# 14_Clocks.net
KiCad netlist of a schematic drawn in Altium Designer
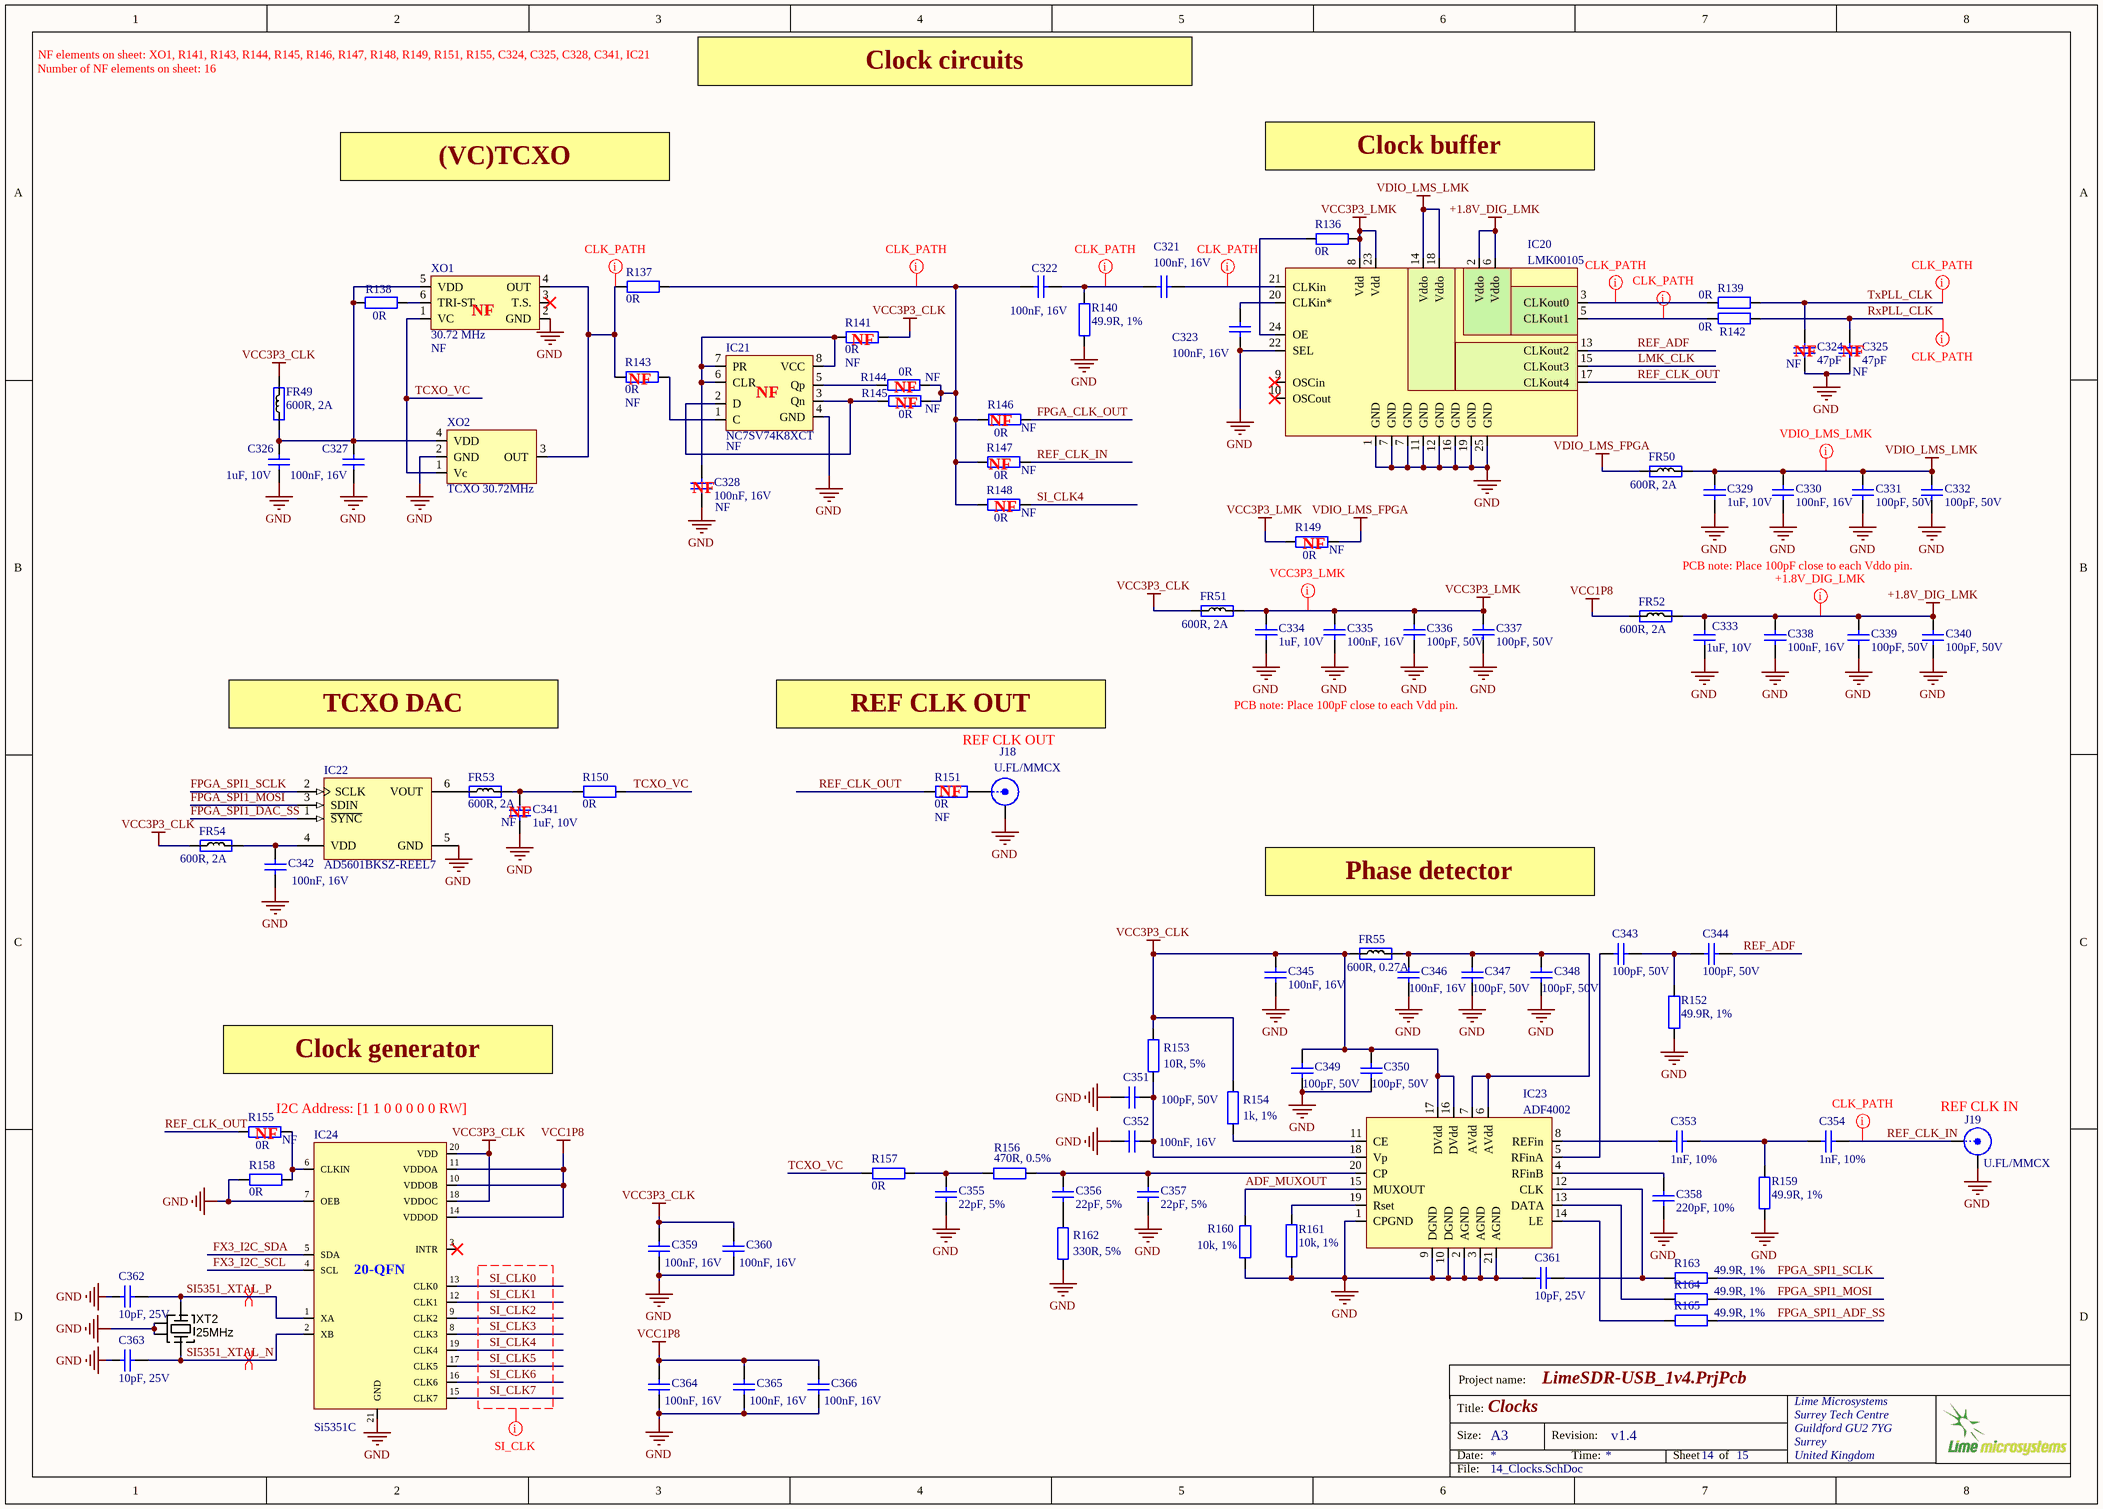
[diagram p0: 14_Clocks.SchDoc]

(export (version "E")
  (design (tool "Eeschema 10.0.6"))
  (components
    (comp (ref "C321")
      (value "100nF, 16V")
      (footprint "CAP0402")
      (fields
        (field (name "MANUFACTURER") "Murata Electronics")
        (field (name "TOLERANCE") "10 %")
        (field (name "MANUFACTURER PART NUMBER") "GRM155R71C104KA88D")
      )
      (libsource (lib "LimeMicroAltiumLib_schLib") (part "Cap_0402"))
    )
    (comp (ref "C322")
      (value "100nF, 16V")
      (footprint "CAP0402")
      (fields
        (field (name "MANUFACTURER") "Murata Electronics")
        (field (name "TOLERANCE") "10 %")
        (field (name "MANUFACTURER PART NUMBER") "GRM155R71C104KA88D")
      )
      (libsource (lib "LimeMicroAltiumLib_schLib") (part "Cap_0402"))
    )
    (comp (ref "C323")
      (value "100nF, 16V")
      (footprint "CAP0402")
      (fields
        (field (name "MANUFACTURER") "Murata Electronics")
        (field (name "TOLERANCE") "10 %")
        (field (name "MANUFACTURER PART NUMBER") "GRM155R71C104KA88D")
      )
      (libsource (lib "LimeMicroAltiumLib_schLib") (part "Cap_0402"))
    )
    (comp (ref "C324")
      (value "47pF")
      (footprint "CAP0402")
      (fields
        (field (name "TOLERANCE") "±1%")
        (field (name "MANUFACTURER") "TDK Corporation")
        (field (name "ASSEMBLY INFO") "NF")
      )
      (libsource (lib "LimeMicroAltiumLib_schLib") (part "Cap_0402"))
    )
    (comp (ref "C325")
      (value "47pF")
      (footprint "CAP0402")
      (fields
        (field (name "TOLERANCE") "±1%")
        (field (name "MANUFACTURER") "TDK Corporation")
        (field (name "ASSEMBLY INFO") "NF")
      )
      (libsource (lib "LimeMicroAltiumLib_schLib") (part "Cap_0402"))
    )
    (comp (ref "C326")
      (value "1uF, 10V")
      (footprint "CAP0402")
      (fields (field (name "MANUFACTURER") "TDK"))
      (libsource (lib "LimeMicroAltiumLib_schLib") (part "Cap_0402"))
    )
    (comp (ref "C327")
      (value "100nF, 16V")
      (footprint "CAP0402")
      (fields
        (field (name "MANUFACTURER") "Murata Electronics")
        (field (name "TOLERANCE") "10 %")
        (field (name "MANUFACTURER PART NUMBER") "GRM155R71C104KA88D")
      )
      (libsource (lib "LimeMicroAltiumLib_schLib") (part "Cap_0402"))
    )
    (comp (ref "C328")
      (value "100nF, 16V")
      (footprint "CAP0402")
      (fields
        (field (name "ASSEMBLY INFO") "NF")
        (field (name "MANUFACTURER") "Murata Electronics")
        (field (name "TOLERANCE") "10 %")
        (field (name "MANUFACTURER PART NUMBER") "GRM155R71C104KA88D")
      )
      (libsource (lib "LimeMicroAltiumLib_schLib") (part "Cap_0402"))
    )
    (comp (ref "C329")
      (value "1uF, 10V")
      (footprint "CAP0402")
      (fields (field (name "MANUFACTURER") "TDK"))
      (libsource (lib "LimeMicroAltiumLib_schLib") (part "Cap_0402"))
    )
    (comp (ref "C330")
      (value "100nF, 16V")
      (footprint "CAP0402")
      (fields
        (field (name "MANUFACTURER") "Murata Electronics")
        (field (name "TOLERANCE") "10 %")
        (field (name "MANUFACTURER PART NUMBER") "GRM155R71C104KA88D")
      )
      (libsource (lib "LimeMicroAltiumLib_schLib") (part "Cap_0402"))
    )
    (comp (ref "C331")
      (value "100pF, 50V")
      (footprint "CAP0402")
      (fields (field (name "MANUFACTURER") "Yageo") (field (name "TOLERANCE") "±5%"))
      (libsource (lib "LimeMicroAltiumLib_schLib") (part "Cap_0402"))
    )
    (comp (ref "C332")
      (value "100pF, 50V")
      (footprint "CAP0402")
      (fields (field (name "MANUFACTURER") "Yageo") (field (name "TOLERANCE") "±5%"))
      (libsource (lib "LimeMicroAltiumLib_schLib") (part "Cap_0402"))
    )
    (comp (ref "C333")
      (value "1uF, 10V")
      (footprint "CAP0402")
      (fields (field (name "MANUFACTURER") "TDK"))
      (libsource (lib "LimeMicroAltiumLib_schLib") (part "Cap_0402"))
    )
    (comp (ref "C334")
      (value "1uF, 10V")
      (footprint "CAP0402")
      (fields (field (name "MANUFACTURER") "TDK"))
      (libsource (lib "LimeMicroAltiumLib_schLib") (part "Cap_0402"))
    )
    (comp (ref "C335")
      (value "100nF, 16V")
      (footprint "CAP0402")
      (fields
        (field (name "MANUFACTURER") "Murata Electronics")
        (field (name "TOLERANCE") "10 %")
        (field (name "MANUFACTURER PART NUMBER") "GRM155R71C104KA88D")
      )
      (libsource (lib "LimeMicroAltiumLib_schLib") (part "Cap_0402"))
    )
    (comp (ref "C336")
      (value "100pF, 50V")
      (footprint "CAP0402")
      (fields (field (name "MANUFACTURER") "Yageo") (field (name "TOLERANCE") "±5%"))
      (libsource (lib "LimeMicroAltiumLib_schLib") (part "Cap_0402"))
    )
    (comp (ref "C337")
      (value "100pF, 50V")
      (footprint "CAP0402")
      (fields (field (name "MANUFACTURER") "Yageo") (field (name "TOLERANCE") "±5%"))
      (libsource (lib "LimeMicroAltiumLib_schLib") (part "Cap_0402"))
    )
    (comp (ref "C338")
      (value "100nF, 16V")
      (footprint "CAP0402")
      (fields
        (field (name "MANUFACTURER") "Murata Electronics")
        (field (name "TOLERANCE") "10 %")
        (field (name "MANUFACTURER PART NUMBER") "GRM155R71C104KA88D")
      )
      (libsource (lib "LimeMicroAltiumLib_schLib") (part "Cap_0402"))
    )
    (comp (ref "C339")
      (value "100pF, 50V")
      (footprint "CAP0402")
      (fields (field (name "MANUFACTURER") "Yageo") (field (name "TOLERANCE") "±5%"))
      (libsource (lib "LimeMicroAltiumLib_schLib") (part "Cap_0402"))
    )
    (comp (ref "C340")
      (value "100pF, 50V")
      (footprint "CAP0402")
      (fields (field (name "MANUFACTURER") "Yageo") (field (name "TOLERANCE") "±5%"))
      (libsource (lib "LimeMicroAltiumLib_schLib") (part "Cap_0402"))
    )
    (comp (ref "C341")
      (value "1uF, 10V")
      (footprint "CAP0402")
      (fields (field (name "ASSEMBLY INFO") "NF") (field (name "MANUFACTURER") "TDK"))
      (libsource (lib "LimeMicroAltiumLib_schLib") (part "Cap_0402"))
    )
    (comp (ref "C342")
      (value "100nF, 16V")
      (footprint "CAP0402")
      (fields
        (field (name "TOLERANCE") "10 %")
        (field (name "MANUFACTURER") "Murata Electronics")
        (field (name "MANUFACTURER PART NUMBER") "GRM155R71C104KA88D")
      )
      (libsource (lib "LimeFPGAboard_schLib") (part "Cap_0603"))
    )
    (comp (ref "C343")
      (value "100pF, 50V")
      (footprint "CAP0402")
      (fields (field (name "MANUFACTURER") "Yageo") (field (name "TOLERANCE") "±5%"))
      (libsource (lib "LimeMicroAltiumLib_schLib") (part "Cap_0402"))
    )
    (comp (ref "C344")
      (value "100pF, 50V")
      (footprint "CAP0402")
      (fields (field (name "MANUFACTURER") "Yageo") (field (name "TOLERANCE") "±5%"))
      (libsource (lib "LimeMicroAltiumLib_schLib") (part "Cap_0402"))
    )
    (comp (ref "C345")
      (value "100nF, 16V")
      (footprint "CAP0402")
      (fields
        (field (name "MANUFACTURER") "Murata Electronics")
        (field (name "TOLERANCE") "10 %")
        (field (name "MANUFACTURER PART NUMBER") "GRM155R71C104KA88D")
      )
      (libsource (lib "LimeMicroAltiumLib_schLib") (part "Cap_0402"))
    )
    (comp (ref "C346")
      (value "100nF, 16V")
      (footprint "CAP0402")
      (fields
        (field (name "MANUFACTURER") "Murata Electronics")
        (field (name "TOLERANCE") "10 %")
        (field (name "MANUFACTURER PART NUMBER") "GRM155R71C104KA88D")
      )
      (libsource (lib "LimeMicroAltiumLib_schLib") (part "Cap_0402"))
    )
    (comp (ref "C347")
      (value "100pF, 50V")
      (footprint "CAP0402")
      (fields (field (name "MANUFACTURER") "Yageo") (field (name "TOLERANCE") "±5%"))
      (libsource (lib "LimeMicroAltiumLib_schLib") (part "Cap_0402"))
    )
    (comp (ref "C348")
      (value "100pF, 50V")
      (footprint "CAP0402")
      (fields (field (name "MANUFACTURER") "Yageo") (field (name "TOLERANCE") "±5%"))
      (libsource (lib "LimeMicroAltiumLib_schLib") (part "Cap_0402"))
    )
    (comp (ref "C349")
      (value "100pF, 50V")
      (footprint "CAP0402")
      (fields (field (name "MANUFACTURER") "Yageo") (field (name "TOLERANCE") "±5%"))
      (libsource (lib "LimeMicroAltiumLib_schLib") (part "Cap_0402"))
    )
    (comp (ref "C350")
      (value "100pF, 50V")
      (footprint "CAP0402")
      (fields (field (name "MANUFACTURER") "Yageo") (field (name "TOLERANCE") "±5%"))
      (libsource (lib "LimeMicroAltiumLib_schLib") (part "Cap_0402"))
    )
    (comp (ref "C351")
      (value "100pF, 50V")
      (footprint "CAP0402")
      (fields (field (name "MANUFACTURER") "Yageo") (field (name "TOLERANCE") "±5%"))
      (libsource (lib "LimeMicroAltiumLib_schLib") (part "Cap_0402"))
    )
    (comp (ref "C352")
      (value "100nF, 16V")
      (footprint "CAP0402")
      (fields
        (field (name "MANUFACTURER") "Murata Electronics")
        (field (name "TOLERANCE") "10 %")
        (field (name "MANUFACTURER PART NUMBER") "GRM155R71C104KA88D")
      )
      (libsource (lib "LimeMicroAltiumLib_schLib") (part "Cap_0402"))
    )
    (comp (ref "C353")
      (value "1nF, 10%")
      (footprint "CAP0402")
      (fields (field (name "TOLERANCE") "10 %") (field (name "MANUFACTURER") "Murata Electronics"))
      (libsource (lib "LimeMicroAltiumLib_schLib") (part "Cap_0402"))
    )
    (comp (ref "C354")
      (value "1nF, 10%")
      (footprint "CAP0402")
      (fields (field (name "TOLERANCE") "10 %") (field (name "MANUFACTURER") "Murata Electronics"))
      (libsource (lib "LimeMicroAltiumLib_schLib") (part "Cap_0402"))
    )
    (comp (ref "C355")
      (value "22pF, 5%")
      (footprint "CAP0402")
      (fields (field (name "TOLERANCE") "±5%") (field (name "MANUFACTURER") "Yageo"))
      (libsource (lib "LimeMicroAltiumLib_schLib") (part "Cap_0402"))
    )
    (comp (ref "C356")
      (value "22pF, 5%")
      (footprint "CAP0402")
      (fields (field (name "TOLERANCE") "±5%") (field (name "MANUFACTURER") "Yageo"))
      (libsource (lib "LimeMicroAltiumLib_schLib") (part "Cap_0402"))
    )
    (comp (ref "C357")
      (value "22pF, 5%")
      (footprint "CAP0402")
      (fields (field (name "TOLERANCE") "±5%") (field (name "MANUFACTURER") "Yageo"))
      (libsource (lib "LimeMicroAltiumLib_schLib") (part "Cap_0402"))
    )
    (comp (ref "C358")
      (value "220pF, 10%")
      (footprint "CAP0402")
      (fields (field (name "MANUFACTURER") "Yageo") (field (name "TOLERANCE") "±10%"))
      (libsource (lib "LimeMicroAltiumLib_schLib") (part "Cap_0402"))
    )
    (comp (ref "C359")
      (value "100nF, 16V")
      (footprint "CAP0402")
      (fields
        (field (name "TOLERANCE") "10 %")
        (field (name "MANUFACTURER") "Murata Electronics")
        (field (name "MANUFACTURER PART NUMBER") "GRM155R71C104KA88D")
      )
      (libsource (lib "LimeFPGAboard_schLib") (part "Cap_0603"))
    )
    (comp (ref "C360")
      (value "100nF, 16V")
      (footprint "CAP0402")
      (fields
        (field (name "TOLERANCE") "10 %")
        (field (name "MANUFACTURER") "Murata Electronics")
        (field (name "MANUFACTURER PART NUMBER") "GRM155R71C104KA88D")
      )
      (libsource (lib "LimeFPGAboard_schLib") (part "Cap_0603"))
    )
    (comp (ref "C361")
      (value "10pF, 25V")
      (footprint "CAP0402")
      (fields (field (name "MANUFACTURER") "AVX"))
      (libsource (lib "LimeMicroAltiumLib_schLib") (part "Cap_0402"))
    )
    (comp (ref "C362")
      (value "10pF, 25V")
      (footprint "CAP0402")
      (fields (field (name "MANUFACTURER") "AVX"))
      (libsource (lib "LimeFPGAboard_schLib") (part "Cap_0402"))
    )
    (comp (ref "C363")
      (value "10pF, 25V")
      (footprint "CAP0402")
      (fields (field (name "MANUFACTURER") "AVX"))
      (libsource (lib "LimeFPGAboard_schLib") (part "Cap_0402"))
    )
    (comp (ref "C364")
      (value "100nF, 16V")
      (footprint "CAP0402")
      (fields
        (field (name "TOLERANCE") "10 %")
        (field (name "MANUFACTURER") "Murata Electronics")
        (field (name "MANUFACTURER PART NUMBER") "GRM155R71C104KA88D")
      )
      (libsource (lib "LimeFPGAboard_schLib") (part "Cap_0603"))
    )
    (comp (ref "C365")
      (value "100nF, 16V")
      (footprint "CAP0402")
      (fields
        (field (name "TOLERANCE") "10 %")
        (field (name "MANUFACTURER") "Murata Electronics")
        (field (name "MANUFACTURER PART NUMBER") "GRM155R71C104KA88D")
      )
      (libsource (lib "LimeFPGAboard_schLib") (part "Cap_0603"))
    )
    (comp (ref "C366")
      (value "100nF, 16V")
      (footprint "CAP0402")
      (fields
        (field (name "TOLERANCE") "10 %")
        (field (name "MANUFACTURER") "Murata Electronics")
        (field (name "MANUFACTURER PART NUMBER") "GRM155R71C104KA88D")
      )
      (libsource (lib "LimeFPGAboard_schLib") (part "Cap_0603"))
    )
    (comp (ref "FR49")
      (value "600R, 2A")
      (footprint "RES0805")
      (fields (field (name "MANUFACTURER") "TDK Corporation"))
      (libsource (lib "LimeMicroAltiumLib_schLib") (part "Ferrite"))
    )
    (comp (ref "FR50")
      (value "600R, 2A")
      (footprint "RES0805")
      (fields (field (name "MANUFACTURER") "TDK Corporation"))
      (libsource (lib "LimeMicroAltiumLib_schLib") (part "Ferrite"))
    )
    (comp (ref "FR51")
      (value "600R, 2A")
      (footprint "RES0805")
      (fields (field (name "MANUFACTURER") "TDK Corporation"))
      (libsource (lib "LimeMicroAltiumLib_schLib") (part "Ferrite"))
    )
    (comp (ref "FR52")
      (value "600R, 2A")
      (footprint "RES0805")
      (fields (field (name "MANUFACTURER") "TDK Corporation"))
      (libsource (lib "LimeMicroAltiumLib_schLib") (part "Ferrite"))
    )
    (comp (ref "FR53")
      (value "600R, 2A")
      (footprint "RES0805")
      (fields (field (name "MANUFACTURER") "TDK Corporation"))
      (libsource (lib "LimeMicroAltiumLib_schLib") (part "Ferrite"))
    )
    (comp (ref "FR54")
      (value "600R, 2A")
      (footprint "RES0805")
      (fields (field (name "MANUFACTURER") "TDK Corporation"))
      (libsource (lib "LimeMicroAltiumLib_schLib") (part "Ferrite"))
    )
    (comp (ref "FR55")
      (value "600R, 0.27A")
      (footprint "RES0201")
      (fields (field (name "MANUFACTURER") "Taiyo Yuden"))
      (libsource (lib "LimeMicroAltiumLib_schLib") (part "Ferrite"))
    )
    (comp (ref "IC20")
      (value "LMK00105")
      (footprint "LMK00105SQ")
      (fields (field (name "MANUFACTURER") "Texas Instruments"))
      (libsource (lib "LimeMicroAltiumLib_schLib") (part "LMK00105"))
    )
    (comp (ref "IC21")
      (value "NC7SV74K8XCT")
      (footprint "NC7SV74K8XCT")
      (fields (field (name "MANUFACTURER") "Fairchild Semiconductor") (field (name "ASSEMBLY INFO") "NF"))
      (libsource (lib "LimeMicroAltiumLib_schLib") (part "NC7SV74K8XCT"))
    )
    (comp (ref "IC22")
      (value "AD5601BKSZ-REEL7")
      (footprint "AD5601_SOT23-6")
      (fields (field (name "GENERIC PART NUMBER") "AD5601") (field (name "MANUFACTURER") "Analog Devices"))
      (libsource (lib "LimeMicroAltiumLib_schLib") (part "AD5601BKSZ-REEL7"))
    )
    (comp (ref "IC23")
      (value "ADF4002")
      (footprint "ADF4002")
      (fields (field (name "MANUFACTURER") "Analog Devices Inc"))
      (libsource (lib "LimeMicroAltiumLib_schLib") (part "ADF4002"))
    )
    (comp (ref "IC24")
      (value "Si5351C")
      (footprint "Si5351C_20QFN")
      (fields (field (name "MANUFACTURER") "Silicon Labs"))
      (libsource (lib "LimeFPGAboard_schLib") (part "Si5351C"))
    )
    (comp (ref "J18")
      (value "U.FL/MMCX")
      (footprint "MMCX_UFL_conn_u")
      (fields (field (name "MANUFACTURER") "Molex, LLC"))
      (libsource (lib "LimeMicroAltiumLib_schLib") (part "RF_IF_connector"))
    )
    (comp (ref "J19")
      (value "U.FL/MMCX")
      (footprint "MMCX_UFL_conn_u")
      (fields (field (name "MANUFACTURER") "Molex, LLC"))
      (libsource (lib "LimeMicroAltiumLib_schLib") (part "RF_IF_connector"))
    )
    (comp (ref "R136")
      (value "0R")
      (footprint "RES0402")
      (fields (field (name "MANUFACTURER") "Yageo") (field (name "TOLERANCE") "Jumper"))
      (libsource (lib "LimeMicroAltiumLib_schLib") (part "Res_0402"))
    )
    (comp (ref "R137")
      (value "0R")
      (footprint "RES0402")
      (fields (field (name "MANUFACTURER") "Yageo") (field (name "TOLERANCE") "Jumper"))
      (libsource (lib "LimeMicroAltiumLib_schLib") (part "Res_0402"))
    )
    (comp (ref "R138")
      (value "0R")
      (footprint "RES0402")
      (fields (field (name "MANUFACTURER") "Yageo") (field (name "TOLERANCE") "Jumper"))
      (libsource (lib "LimeMicroAltiumLib_schLib") (part "Res_0402"))
    )
    (comp (ref "R139")
      (value "0R")
      (footprint "RES0402")
      (fields (field (name "MANUFACTURER") "Yageo") (field (name "TOLERANCE") "Jumper"))
      (libsource (lib "LimeMicroAltiumLib_schLib") (part "Res_0402"))
    )
    (comp (ref "R140")
      (value "49.9R, 1%")
      (footprint "RES0402")
      (fields
        (field (name "TOLERANCE") "±1%")
        (field (name "MANUFACTURER") "Samsung Electro-Mechanics America, Inc.")
        (field (name "MANUFACTURER PART NUMBER") "RC1005F49R9CS")
      )
      (libsource (lib "LimeMicroAltiumLib_schLib") (part "Res_0402"))
    )
    (comp (ref "R141")
      (value "0R")
      (footprint "RES0402")
      (fields
        (field (name "ASSEMBLY INFO") "NF")
        (field (name "MANUFACTURER") "Yageo")
        (field (name "TOLERANCE") "Jumper")
      )
      (libsource (lib "LimeMicroAltiumLib_schLib") (part "Res_0402"))
    )
    (comp (ref "R142")
      (value "0R")
      (footprint "RES0402")
      (fields (field (name "MANUFACTURER") "Yageo") (field (name "TOLERANCE") "Jumper"))
      (libsource (lib "LimeMicroAltiumLib_schLib") (part "Res_0402"))
    )
    (comp (ref "R143")
      (value "0R")
      (footprint "RES0402")
      (fields
        (field (name "ASSEMBLY INFO") "NF")
        (field (name "MANUFACTURER") "Yageo")
        (field (name "TOLERANCE") "Jumper")
      )
      (libsource (lib "LimeMicroAltiumLib_schLib") (part "Res_0402"))
    )
    (comp (ref "R144")
      (value "0R")
      (footprint "RES0402")
      (fields
        (field (name "ASSEMBLY INFO") "NF")
        (field (name "MANUFACTURER") "Yageo")
        (field (name "TOLERANCE") "Jumper")
      )
      (libsource (lib "LimeMicroAltiumLib_schLib") (part "Res_0402"))
    )
    (comp (ref "R145")
      (value "0R")
      (footprint "RES0402")
      (fields
        (field (name "ASSEMBLY INFO") "NF")
        (field (name "MANUFACTURER") "Yageo")
        (field (name "TOLERANCE") "Jumper")
      )
      (libsource (lib "LimeMicroAltiumLib_schLib") (part "Res_0402"))
    )
    (comp (ref "R146")
      (value "0R")
      (footprint "RES0402")
      (fields
        (field (name "ASSEMBLY INFO") "NF")
        (field (name "MANUFACTURER") "Yageo")
        (field (name "TOLERANCE") "Jumper")
      )
      (libsource (lib "LimeMicroAltiumLib_schLib") (part "Res_0402"))
    )
    (comp (ref "R147")
      (value "0R")
      (footprint "RES0402")
      (fields
        (field (name "ASSEMBLY INFO") "NF")
        (field (name "MANUFACTURER") "Yageo")
        (field (name "TOLERANCE") "Jumper")
      )
      (libsource (lib "LimeMicroAltiumLib_schLib") (part "Res_0402"))
    )
    (comp (ref "R148")
      (value "0R")
      (footprint "RES0402")
      (fields
        (field (name "ASSEMBLY INFO") "NF")
        (field (name "MANUFACTURER") "Yageo")
        (field (name "TOLERANCE") "Jumper")
      )
      (libsource (lib "LimeMicroAltiumLib_schLib") (part "Res_0402"))
    )
    (comp (ref "R149")
      (value "0R")
      (footprint "RES0402")
      (fields
        (field (name "ASSEMBLY INFO") "NF")
        (field (name "MANUFACTURER") "Yageo")
        (field (name "TOLERANCE") "Jumper")
      )
      (libsource (lib "LimeMicroAltiumLib_schLib") (part "Res_0402"))
    )
    (comp (ref "R150")
      (value "0R")
      (footprint "RES0402")
      (fields (field (name "MANUFACTURER") "Yageo") (field (name "TOLERANCE") "Jumper"))
      (libsource (lib "LimeMicroAltiumLib_schLib") (part "Res_0402"))
    )
    (comp (ref "R151")
      (value "0R")
      (footprint "RES0402")
      (fields
        (field (name "ASSEMBLY INFO") "NF")
        (field (name "MANUFACTURER") "Yageo")
        (field (name "TOLERANCE") "Jumper")
      )
      (libsource (lib "LimeMicroAltiumLib_schLib") (part "Res_0402"))
    )
    (comp (ref "R152")
      (value "49.9R, 1%")
      (footprint "RES0402")
      (fields
        (field (name "TOLERANCE") "±1%")
        (field (name "MANUFACTURER") "Samsung Electro-Mechanics America, Inc.")
        (field (name "MANUFACTURER PART NUMBER") "RC1005F49R9CS")
      )
      (libsource (lib "LimeMicroAltiumLib_schLib") (part "Res_0402"))
    )
    (comp (ref "R153")
      (value "10R, 5%")
      (footprint "RES0402")
      (fields (field (name "TOLERANCE") "±5%") (field (name "MANUFACTURER") "Yageo"))
      (libsource (lib "LimeMicroAltiumLib_schLib") (part "Res_0402"))
    )
    (comp (ref "R154")
      (value "1k, 1%")
      (footprint "RES0402")
      (fields (field (name "MANUFACTURER") "Stackpole Electronics Inc") (field (name "TOLERANCE") "±1%"))
      (libsource (lib "LimeMicroAltiumLib_schLib") (part "Res_0402"))
    )
    (comp (ref "R155")
      (value "0R")
      (footprint "RES0402")
      (fields
        (field (name "ASSEMBLY INFO") "NF")
        (field (name "MANUFACTURER") "Yageo")
        (field (name "TOLERANCE") "Jumper")
      )
      (libsource (lib "LimeMicroAltiumLib_schLib") (part "Res_0402"))
    )
    (comp (ref "R156")
      (value "470R, 0.5%")
      (footprint "RES0402")
      (fields
        (field (name "TOLERANCE") "±0.5%")
        (field (name "MANUFACTURER") "Panasonic Electronic Components")
      )
      (libsource (lib "LimeMicroAltiumLib_schLib") (part "Res_0402"))
    )
    (comp (ref "R157")
      (value "0R")
      (footprint "RES0402")
      (fields (field (name "MANUFACTURER") "Yageo") (field (name "TOLERANCE") "Jumper"))
      (libsource (lib "LimeMicroAltiumLib_schLib") (part "Res_0402"))
    )
    (comp (ref "R158")
      (value "0R")
      (footprint "RES0402")
      (fields (field (name "MANUFACTURER") "Yageo") (field (name "TOLERANCE") "Jumper"))
      (libsource (lib "LimeMicroAltiumLib_schLib") (part "Res_0402"))
    )
    (comp (ref "R159")
      (value "49.9R, 1%")
      (footprint "RES0402")
      (fields
        (field (name "TOLERANCE") "±1%")
        (field (name "MANUFACTURER") "Samsung Electro-Mechanics America, Inc.")
        (field (name "MANUFACTURER PART NUMBER") "RC1005F49R9CS")
      )
      (libsource (lib "LimeMicroAltiumLib_schLib") (part "Res_0402"))
    )
    (comp (ref "R160")
      (value "10k, 1%")
      (footprint "RES0402")
      (fields (field (name "MANUFACTURER") "Yageo") (field (name "TOLERANCE") "±1%"))
      (libsource (lib "LimeMicroAltiumLib_schLib") (part "Res_0402"))
    )
    (comp (ref "R161")
      (value "10k, 1%")
      (footprint "RES0402")
      (fields (field (name "MANUFACTURER") "Yageo") (field (name "TOLERANCE") "±1%"))
      (libsource (lib "LimeMicroAltiumLib_schLib") (part "Res_0402"))
    )
    (comp (ref "R162")
      (value "330R, 5%")
      (footprint "RES0402")
      (fields (field (name "MANUFACTURER") "Yageo") (field (name "TOLERANCE") "±5%"))
      (libsource (lib "LimeMicroAltiumLib_schLib") (part "Res_0402"))
    )
    (comp (ref "R163")
      (value "49.9R, 1%")
      (footprint "RES0402")
      (fields
        (field (name "TOLERANCE") "±1%")
        (field (name "MANUFACTURER") "Samsung Electro-Mechanics America, Inc.")
        (field (name "MANUFACTURER PART NUMBER") "RC1005F49R9CS")
      )
      (libsource (lib "LimeMicroAltiumLib_schLib") (part "Res_0402"))
    )
    (comp (ref "R164")
      (value "49.9R, 1%")
      (footprint "RES0402")
      (fields
        (field (name "TOLERANCE") "±1%")
        (field (name "MANUFACTURER") "Samsung Electro-Mechanics America, Inc.")
        (field (name "MANUFACTURER PART NUMBER") "RC1005F49R9CS")
      )
      (libsource (lib "LimeMicroAltiumLib_schLib") (part "Res_0402"))
    )
    (comp (ref "R165")
      (value "49.9R, 1%")
      (footprint "RES0402")
      (fields
        (field (name "TOLERANCE") "±1%")
        (field (name "MANUFACTURER") "Samsung Electro-Mechanics America, Inc.")
        (field (name "MANUFACTURER PART NUMBER") "RC1005F49R9CS")
      )
      (libsource (lib "LimeMicroAltiumLib_schLib") (part "Res_0402"))
    )
    (comp (ref "XO1")
      (value "30.72 MHz")
      (footprint "RAKON_RPT7050A")
      (fields (field (name "ASSEMBLY INFO") "NF") (field (name "MANUFACTURER") "Rakon"))
      (libsource (lib "LimeMicroAltiumLib_schLib") (part "RPT7050A"))
    )
    (comp (ref "XO2")
      (value "TCXO 30.72MHz")
      (footprint "RAKON_TXCO")
      (fields (field (name "MANUFACTURER") "Rakon"))
      (libsource (lib "LimeMicroAltiumLib_schLib") (part "TXCO"))
    )
    (comp (ref "XT2")
      (value "25MHz")
      (footprint "CRYSTAL_4-LCC")
      (description "Oscillator Crystal 25 MHz")
      (fields (field (name "MANUFACTURER") "ABRACON"))
      (libsource (lib "LimeFPGAboard_schLib") (part "CRYSTAL_19M2"))
    )
  )
  (nets
    (net (code "1") (name "+1.8V_DIG_LMK") (class "Default")
      (node (ref "C333") (pin "2") (pinfunction "2_2") (pintype "passive"))
      (node (ref "C338") (pin "2") (pinfunction "2_2") (pintype "passive"))
      (node (ref "C339") (pin "2") (pinfunction "2_2") (pintype "passive"))
      (node (ref "C340") (pin "2") (pinfunction "2_2") (pintype "passive"))
      (node (ref "FR52") (pin "2") (pinfunction "2_2") (pintype "passive"))
      (node (ref "IC20") (pin "2") (pinfunction "Vddo_2") (pintype "passive"))
      (node (ref "IC20") (pin "6") (pinfunction "Vddo_6") (pintype "passive"))
    )
    (net (code "2") (name "/ADF_MUXOUT") (class "Default")
      (node (ref "IC23") (pin "15") (pinfunction "MUXOUT_15") (pintype "passive"))
      (node (ref "R160") (pin "1") (pinfunction "1_1") (pintype "passive"))
    )
    (net (code "3") (name "/FPGA_CLK_OUT") (class "Default")
      (node (ref "R146") (pin "1") (pinfunction "1_1") (pintype "passive"))
    )
    (net (code "4") (name "/FPGA_SPI1_ADF_SS") (class "Default")
      (node (ref "R165") (pin "1") (pinfunction "1_1") (pintype "passive"))
    )
    (net (code "5") (name "/FPGA_SPI1_DAC_SS") (class "Default")
      (node (ref "IC22") (pin "1") (pinfunction "~{SYNC}_1") (pintype "input"))
    )
    (net (code "6") (name "/FPGA_SPI1_MOSI") (class "Default")
      (node (ref "IC22") (pin "3") (pinfunction "SDIN_3") (pintype "input"))
      (node (ref "R164") (pin "1") (pinfunction "1_1") (pintype "passive"))
    )
    (net (code "7") (name "/FPGA_SPI1_SCLK") (class "Default")
      (node (ref "IC22") (pin "2") (pinfunction "SCLK_2") (pintype "input"))
      (node (ref "R163") (pin "1") (pinfunction "1_1") (pintype "passive"))
    )
    (net (code "8") (name "/FX3_I2C_SCL") (class "Default")
      (node (ref "IC24") (pin "4") (pinfunction "SCL_4") (pintype "passive"))
    )
    (net (code "9") (name "/FX3_I2C_SDA") (class "Default")
      (node (ref "IC24") (pin "5") (pinfunction "SDA_5") (pintype "passive"))
    )
    (net (code "10") (name "/LMK_CLK") (class "Default")
      (node (ref "IC20") (pin "15") (pinfunction "CLKout3_15") (pintype "passive"))
    )
    (net (code "11") (name "/REF_ADF") (class "Default")
      (node (ref "C344") (pin "2") (pinfunction "2_2") (pintype "passive"))
      (node (ref "IC20") (pin "13") (pinfunction "CLKout2_13") (pintype "passive"))
    )
    (net (code "12") (name "/REF_CLK_IN") (class "Default")
      (node (ref "C354") (pin "1") (pinfunction "1_1") (pintype "passive"))
      (node (ref "J19") (pin "1") (pinfunction "X_1") (pintype "passive"))
      (node (ref "R147") (pin "2") (pinfunction "2_2") (pintype "passive"))
    )
    (net (code "13") (name "/REF_CLK_OUT") (class "Default")
      (node (ref "IC20") (pin "17") (pinfunction "CLKout4_17") (pintype "passive"))
      (node (ref "R151") (pin "2") (pinfunction "2_2") (pintype "passive"))
      (node (ref "R155") (pin "1") (pinfunction "1_1") (pintype "passive"))
    )
    (net (code "14") (name "/RxPLL_CLK") (class "Default")
      (node (ref "C325") (pin "2") (pinfunction "2_2") (pintype "passive"))
      (node (ref "R142") (pin "1") (pinfunction "1_1") (pintype "passive"))
    )
    (net (code "15") (name "/SI5351_XTAL_N") (class "Default")
      (node (ref "C363") (pin "2") (pinfunction "2_2") (pintype "passive"))
      (node (ref "IC24") (pin "2") (pinfunction "XB_2") (pintype "passive"))
      (node (ref "XT2") (pin "3") (pinfunction "X_3") (pintype "passive"))
    )
    (net (code "16") (name "/SI5351_XTAL_P") (class "Default")
      (node (ref "C362") (pin "2") (pinfunction "2_2") (pintype "passive"))
      (node (ref "IC24") (pin "1") (pinfunction "XA_1") (pintype "passive"))
      (node (ref "XT2") (pin "1") (pinfunction "X_1") (pintype "passive"))
    )
    (net (code "17") (name "/SI_CLK0") (class "Default")
      (node (ref "IC24") (pin "13") (pinfunction "CLK0_13") (pintype "passive"))
    )
    (net (code "18") (name "/SI_CLK1") (class "Default")
      (node (ref "IC24") (pin "12") (pinfunction "CLK1_12") (pintype "passive"))
    )
    (net (code "19") (name "/SI_CLK2") (class "Default")
      (node (ref "IC24") (pin "9") (pinfunction "CLK2_9") (pintype "passive"))
    )
    (net (code "20") (name "/SI_CLK3") (class "Default")
      (node (ref "IC24") (pin "8") (pinfunction "CLK3_8") (pintype "passive"))
    )
    (net (code "21") (name "/SI_CLK4") (class "Default")
      (node (ref "IC24") (pin "19") (pinfunction "CLK4_19") (pintype "passive"))
      (node (ref "R148") (pin "2") (pinfunction "2_2") (pintype "passive"))
    )
    (net (code "22") (name "/SI_CLK5") (class "Default")
      (node (ref "IC24") (pin "17") (pinfunction "CLK5_17") (pintype "passive"))
    )
    (net (code "23") (name "/SI_CLK6") (class "Default")
      (node (ref "IC24") (pin "16") (pinfunction "CLK6_16") (pintype "passive"))
    )
    (net (code "24") (name "/SI_CLK7") (class "Default")
      (node (ref "IC24") (pin "15") (pinfunction "CLK7_15") (pintype "passive"))
    )
    (net (code "25") (name "/TCXO_VC") (class "Default")
      (node (ref "R150") (pin "1") (pinfunction "1_1") (pintype "passive"))
      (node (ref "R157") (pin "2") (pinfunction "2_2") (pintype "passive"))
      (node (ref "XO1") (pin "1") (pinfunction "VC_1") (pintype "passive"))
      (node (ref "XO2") (pin "1") (pinfunction "Vc_1") (pintype "passive"))
    )
    (net (code "26") (name "/TxPLL_CLK") (class "Default")
      (node (ref "C324") (pin "2") (pinfunction "2_2") (pintype "passive"))
      (node (ref "R139") (pin "1") (pinfunction "1_1") (pintype "passive"))
    )
    (net (code "27") (name "GND") (class "Default")
      (node (ref "C323") (pin "1") (pinfunction "1_1") (pintype "passive"))
      (node (ref "C324") (pin "1") (pinfunction "1_1") (pintype "passive"))
      (node (ref "C325") (pin "1") (pinfunction "1_1") (pintype "passive"))
      (node (ref "C326") (pin "1") (pinfunction "1_1") (pintype "passive"))
      (node (ref "C327") (pin "1") (pinfunction "1_1") (pintype "passive"))
      (node (ref "C328") (pin "1") (pinfunction "1_1") (pintype "passive"))
      (node (ref "C329") (pin "1") (pinfunction "1_1") (pintype "passive"))
      (node (ref "C330") (pin "1") (pinfunction "1_1") (pintype "passive"))
      (node (ref "C331") (pin "1") (pinfunction "1_1") (pintype "passive"))
      (node (ref "C332") (pin "1") (pinfunction "1_1") (pintype "passive"))
      (node (ref "C333") (pin "1") (pinfunction "1_1") (pintype "passive"))
      (node (ref "C334") (pin "1") (pinfunction "1_1") (pintype "passive"))
      (node (ref "C335") (pin "1") (pinfunction "1_1") (pintype "passive"))
      (node (ref "C336") (pin "1") (pinfunction "1_1") (pintype "passive"))
      (node (ref "C337") (pin "1") (pinfunction "1_1") (pintype "passive"))
      (node (ref "C338") (pin "1") (pinfunction "1_1") (pintype "passive"))
      (node (ref "C339") (pin "1") (pinfunction "1_1") (pintype "passive"))
      (node (ref "C340") (pin "1") (pinfunction "1_1") (pintype "passive"))
      (node (ref "C341") (pin "1") (pinfunction "1_1") (pintype "passive"))
      (node (ref "C342") (pin "2") (pinfunction "2_2") (pintype "passive"))
      (node (ref "C345") (pin "1") (pinfunction "1_1") (pintype "passive"))
      (node (ref "C346") (pin "1") (pinfunction "1_1") (pintype "passive"))
      (node (ref "C347") (pin "2") (pinfunction "2_2") (pintype "passive"))
      (node (ref "C348") (pin "2") (pinfunction "2_2") (pintype "passive"))
      (node (ref "C349") (pin "2") (pinfunction "2_2") (pintype "passive"))
      (node (ref "C350") (pin "2") (pinfunction "2_2") (pintype "passive"))
      (node (ref "C351") (pin "1") (pinfunction "1_1") (pintype "passive"))
      (node (ref "C352") (pin "2") (pinfunction "2_2") (pintype "passive"))
      (node (ref "C355") (pin "1") (pinfunction "1_1") (pintype "passive"))
      (node (ref "C357") (pin "1") (pinfunction "1_1") (pintype "passive"))
      (node (ref "C358") (pin "2") (pinfunction "2_2") (pintype "passive"))
      (node (ref "C359") (pin "2") (pinfunction "2_2") (pintype "passive"))
      (node (ref "C360") (pin "2") (pinfunction "2_2") (pintype "passive"))
      (node (ref "C361") (pin "1") (pinfunction "1_1") (pintype "passive"))
      (node (ref "C362") (pin "1") (pinfunction "1_1") (pintype "passive"))
      (node (ref "C363") (pin "1") (pinfunction "1_1") (pintype "passive"))
      (node (ref "C364") (pin "2") (pinfunction "2_2") (pintype "passive"))
      (node (ref "C365") (pin "2") (pinfunction "2_2") (pintype "passive"))
      (node (ref "C366") (pin "2") (pinfunction "2_2") (pintype "passive"))
      (node (ref "IC20") (pin "1") (pinfunction "GND_1") (pintype "passive"))
      (node (ref "IC20") (pin "11") (pinfunction "GND_11") (pintype "passive"))
      (node (ref "IC20") (pin "12") (pinfunction "GND_12") (pintype "passive"))
      (node (ref "IC20") (pin "16") (pinfunction "GND_16") (pintype "passive"))
      (node (ref "IC20") (pin "19") (pinfunction "GND_19") (pintype "passive"))
      (node (ref "IC20") (pin "22") (pinfunction "SEL_22") (pintype "passive"))
      (node (ref "IC20") (pin "25") (pinfunction "GND_25") (pintype "passive"))
      (node (ref "IC20") (pin "7") (pinfunction "GND_7") (pintype "passive"))
      (node (ref "IC21") (pin "4") (pinfunction "GND_4") (pintype "passive"))
      (node (ref "IC22") (pin "5") (pinfunction "GND_5") (pintype "power_in"))
      (node (ref "IC23") (pin "1") (pinfunction "CPGND_1") (pintype "passive"))
      (node (ref "IC23") (pin "10") (pinfunction "DGND_10") (pintype "passive"))
      (node (ref "IC23") (pin "2") (pinfunction "AGND_2") (pintype "passive"))
      (node (ref "IC23") (pin "21") (pinfunction "AGND_21") (pintype "passive"))
      (node (ref "IC23") (pin "3") (pinfunction "AGND_3") (pintype "passive"))
      (node (ref "IC23") (pin "9") (pinfunction "DGND_9") (pintype "passive"))
      (node (ref "IC24") (pin "21") (pinfunction "GND_21") (pintype "passive"))
      (node (ref "IC24") (pin "7") (pinfunction "OEB_7") (pintype "passive"))
      (node (ref "J18") (pin "2") (pinfunction "Y_2") (pintype "passive"))
      (node (ref "J19") (pin "2") (pinfunction "Y_2") (pintype "passive"))
      (node (ref "R140") (pin "1") (pinfunction "1_1") (pintype "passive"))
      (node (ref "R152") (pin "1") (pinfunction "1_1") (pintype "passive"))
      (node (ref "R158") (pin "2") (pinfunction "2_2") (pintype "passive"))
      (node (ref "R159") (pin "1") (pinfunction "1_1") (pintype "passive"))
      (node (ref "R160") (pin "2") (pinfunction "2_2") (pintype "passive"))
      (node (ref "R161") (pin "2") (pinfunction "2_2") (pintype "passive"))
      (node (ref "R162") (pin "1") (pinfunction "1_1") (pintype "passive"))
      (node (ref "XO1") (pin "2") (pinfunction "GND_2") (pintype "passive"))
      (node (ref "XO2") (pin "2") (pinfunction "GND_2") (pintype "passive"))
      (node (ref "XT2") (pin "2") (pinfunction "GND_2") (pintype "passive"))
      (node (ref "XT2") (pin "4") (pinfunction "GND_4") (pintype "passive"))
    )
    (net (code "28") (name "Net-(C321-Pad2)") (class "Default")
      (node (ref "C321") (pin "2") (pinfunction "2_2") (pintype "passive"))
      (node (ref "C322") (pin "1") (pinfunction "1_1") (pintype "passive"))
      (node (ref "R140") (pin "2") (pinfunction "2_2") (pintype "passive"))
    )
    (net (code "29") (name "Net-(C322-Pad2)") (class "Default")
      (node (ref "C322") (pin "2") (pinfunction "2_2") (pintype "passive"))
      (node (ref "R137") (pin "1") (pinfunction "1_1") (pintype "passive"))
      (node (ref "R144") (pin "1") (pinfunction "1_1") (pintype "passive"))
      (node (ref "R145") (pin "1") (pinfunction "1_1") (pintype "passive"))
      (node (ref "R146") (pin "2") (pinfunction "2_2") (pintype "passive"))
      (node (ref "R147") (pin "1") (pinfunction "1_1") (pintype "passive"))
      (node (ref "R148") (pin "1") (pinfunction "1_1") (pintype "passive"))
    )
    (net (code "30") (name "Net-(C341-Pad2)") (class "Default")
      (node (ref "C341") (pin "2") (pinfunction "2_2") (pintype "passive"))
      (node (ref "FR53") (pin "2") (pinfunction "2_2") (pintype "passive"))
      (node (ref "R150") (pin "2") (pinfunction "2_2") (pintype "passive"))
    )
    (net (code "31") (name "Net-(C343-Pad2)") (class "Default")
      (node (ref "C343") (pin "2") (pinfunction "2_2") (pintype "passive"))
      (node (ref "C344") (pin "1") (pinfunction "1_1") (pintype "passive"))
      (node (ref "R152") (pin "2") (pinfunction "2_2") (pintype "passive"))
    )
    (net (code "32") (name "Net-(C346-Pad2)") (class "Default")
      (node (ref "C346") (pin "2") (pinfunction "2_2") (pintype "passive"))
      (node (ref "C347") (pin "1") (pinfunction "1_1") (pintype "passive"))
      (node (ref "C348") (pin "1") (pinfunction "1_1") (pintype "passive"))
      (node (ref "FR55") (pin "2") (pinfunction "2_2") (pintype "passive"))
      (node (ref "IC23") (pin "6") (pinfunction "AVdd_6") (pintype "passive"))
      (node (ref "IC23") (pin "7") (pinfunction "AVdd_7") (pintype "passive"))
    )
    (net (code "33") (name "Net-(C353-Pad1)") (class "Default")
      (node (ref "C353") (pin "1") (pinfunction "1_1") (pintype "passive"))
      (node (ref "C354") (pin "2") (pinfunction "2_2") (pintype "passive"))
      (node (ref "R159") (pin "2") (pinfunction "2_2") (pintype "passive"))
    )
    (net (code "34") (name "Net-(C355-Pad2)") (class "Default")
      (node (ref "C355") (pin "2") (pinfunction "2_2") (pintype "passive"))
      (node (ref "R156") (pin "2") (pinfunction "2_2") (pintype "passive"))
      (node (ref "R157") (pin "1") (pinfunction "1_1") (pintype "passive"))
    )
    (net (code "35") (name "Net-(C356-Pad1)") (class "Default")
      (node (ref "C356") (pin "1") (pinfunction "1_1") (pintype "passive"))
      (node (ref "R162") (pin "2") (pinfunction "2_2") (pintype "passive"))
    )
    (net (code "36") (name "Net-(IC20-CLKin)") (class "Default")
      (node (ref "C321") (pin "1") (pinfunction "1_1") (pintype "passive"))
      (node (ref "IC20") (pin "21") (pinfunction "CLKin_21") (pintype "passive"))
    )
    (net (code "37") (name "Net-(IC20-CLKin*)") (class "Default")
      (node (ref "C323") (pin "2") (pinfunction "2_2") (pintype "passive"))
      (node (ref "IC20") (pin "20") (pinfunction "CLKin*_20") (pintype "passive"))
    )
    (net (code "38") (name "Net-(IC20-CLKout0)") (class "Default")
      (node (ref "IC20") (pin "3") (pinfunction "CLKout0_3") (pintype "passive"))
      (node (ref "R139") (pin "2") (pinfunction "2_2") (pintype "passive"))
    )
    (net (code "39") (name "Net-(IC20-CLKout1)") (class "Default")
      (node (ref "IC20") (pin "5") (pinfunction "CLKout1_5") (pintype "passive"))
      (node (ref "R142") (pin "2") (pinfunction "2_2") (pintype "passive"))
    )
    (net (code "40") (name "Net-(IC20-OE)") (class "Default")
      (node (ref "IC20") (pin "24") (pinfunction "OE_24") (pintype "passive"))
      (node (ref "R136") (pin "1") (pinfunction "1_1") (pintype "passive"))
    )
    (net (code "41") (name "Net-(IC21-C)") (class "Default")
      (node (ref "IC21") (pin "1") (pinfunction "C_1") (pintype "passive"))
      (node (ref "R143") (pin "1") (pinfunction "1_1") (pintype "passive"))
    )
    (net (code "42") (name "Net-(IC21-CLR)") (class "Default")
      (node (ref "C328") (pin "2") (pinfunction "2_2") (pintype "passive"))
      (node (ref "IC21") (pin "6") (pinfunction "CLR_6") (pintype "passive"))
      (node (ref "IC21") (pin "7") (pinfunction "PR_7") (pintype "passive"))
      (node (ref "IC21") (pin "8") (pinfunction "VCC_8") (pintype "passive"))
      (node (ref "R141") (pin "2") (pinfunction "2_2") (pintype "passive"))
    )
    (net (code "43") (name "Net-(IC21-D)") (class "Default")
      (node (ref "IC21") (pin "2") (pinfunction "D_2") (pintype "passive"))
      (node (ref "IC21") (pin "3") (pinfunction "Qn_3") (pintype "passive"))
      (node (ref "R145") (pin "2") (pinfunction "2_2") (pintype "passive"))
    )
    (net (code "44") (name "Net-(IC21-Qp)") (class "Default")
      (node (ref "IC21") (pin "5") (pinfunction "Qp_5") (pintype "passive"))
      (node (ref "R144") (pin "2") (pinfunction "2_2") (pintype "passive"))
    )
    (net (code "45") (name "Net-(IC22-VDD)") (class "Default")
      (node (ref "C342") (pin "1") (pinfunction "1_1") (pintype "passive"))
      (node (ref "FR54") (pin "2") (pinfunction "2_2") (pintype "passive"))
      (node (ref "IC22") (pin "4") (pinfunction "VDD_4") (pintype "power_in"))
    )
    (net (code "46") (name "Net-(IC22-VOUT)") (class "Default")
      (node (ref "FR53") (pin "1") (pinfunction "1_1") (pintype "passive"))
      (node (ref "IC22") (pin "6") (pinfunction "VOUT_6") (pintype "tri_state"))
    )
    (net (code "47") (name "Net-(IC23-CE)") (class "Default")
      (node (ref "IC23") (pin "11") (pinfunction "CE_11") (pintype "passive"))
      (node (ref "R154") (pin "1") (pinfunction "1_1") (pintype "passive"))
    )
    (net (code "48") (name "Net-(IC23-CLK)") (class "Default")
      (node (ref "C361") (pin "2") (pinfunction "2_2") (pintype "passive"))
      (node (ref "IC23") (pin "12") (pinfunction "CLK_12") (pintype "passive"))
      (node (ref "R163") (pin "2") (pinfunction "2_2") (pintype "passive"))
    )
    (net (code "49") (name "Net-(IC23-CP)") (class "Default")
      (node (ref "C356") (pin "2") (pinfunction "2_2") (pintype "passive"))
      (node (ref "C357") (pin "2") (pinfunction "2_2") (pintype "passive"))
      (node (ref "IC23") (pin "20") (pinfunction "CP_20") (pintype "passive"))
      (node (ref "R156") (pin "1") (pinfunction "1_1") (pintype "passive"))
    )
    (net (code "50") (name "Net-(IC23-DATA)") (class "Default")
      (node (ref "IC23") (pin "13") (pinfunction "DATA_13") (pintype "passive"))
      (node (ref "R164") (pin "2") (pinfunction "2_2") (pintype "passive"))
    )
    (net (code "51") (name "Net-(IC23-LE)") (class "Default")
      (node (ref "IC23") (pin "14") (pinfunction "LE_14") (pintype "passive"))
      (node (ref "R165") (pin "2") (pinfunction "2_2") (pintype "passive"))
    )
    (net (code "52") (name "Net-(IC23-REFin)") (class "Default")
      (node (ref "C353") (pin "2") (pinfunction "2_2") (pintype "passive"))
      (node (ref "IC23") (pin "8") (pinfunction "REFin_8") (pintype "passive"))
    )
    (net (code "53") (name "Net-(IC23-RFinA)") (class "Default")
      (node (ref "C343") (pin "1") (pinfunction "1_1") (pintype "passive"))
      (node (ref "IC23") (pin "5") (pinfunction "RFinA_5") (pintype "passive"))
    )
    (net (code "54") (name "Net-(IC23-RFinB)") (class "Default")
      (node (ref "C358") (pin "1") (pinfunction "1_1") (pintype "passive"))
      (node (ref "IC23") (pin "4") (pinfunction "RFinB_4") (pintype "passive"))
    )
    (net (code "55") (name "Net-(IC23-Rset)") (class "Default")
      (node (ref "IC23") (pin "19") (pinfunction "Rset_19") (pintype "passive"))
      (node (ref "R161") (pin "1") (pinfunction "1_1") (pintype "passive"))
    )
    (net (code "56") (name "Net-(IC23-Vp)") (class "Default")
      (node (ref "C351") (pin "2") (pinfunction "2_2") (pintype "passive"))
      (node (ref "C352") (pin "1") (pinfunction "1_1") (pintype "passive"))
      (node (ref "IC23") (pin "18") (pinfunction "Vp_18") (pintype "passive"))
      (node (ref "R153") (pin "1") (pinfunction "1_1") (pintype "passive"))
    )
    (net (code "57") (name "Net-(IC24-CLKIN)") (class "Default")
      (node (ref "IC24") (pin "6") (pinfunction "CLKIN_6") (pintype "passive"))
      (node (ref "R155") (pin "2") (pinfunction "2_2") (pintype "passive"))
      (node (ref "R158") (pin "1") (pinfunction "1_1") (pintype "passive"))
    )
    (net (code "58") (name "Net-(J18-X)") (class "Default")
      (node (ref "J18") (pin "1") (pinfunction "X_1") (pintype "passive"))
      (node (ref "R151") (pin "1") (pinfunction "1_1") (pintype "passive"))
    )
    (net (code "59") (name "Net-(XO1-OUT)") (class "Default")
      (node (ref "R137") (pin "2") (pinfunction "2_2") (pintype "passive"))
      (node (ref "R143") (pin "2") (pinfunction "2_2") (pintype "passive"))
      (node (ref "XO1") (pin "4") (pinfunction "OUT_4") (pintype "passive"))
      (node (ref "XO2") (pin "3") (pinfunction "OUT_3") (pintype "passive"))
    )
    (net (code "60") (name "Net-(XO1-TRI-ST.)") (class "Default")
      (node (ref "R138") (pin "1") (pinfunction "1_1") (pintype "passive"))
      (node (ref "XO1") (pin "6") (pinfunction "TRI-ST._6") (pintype "passive"))
    )
    (net (code "61") (name "Net-(XO1-VDD)") (class "Default")
      (node (ref "C326") (pin "2") (pinfunction "2_2") (pintype "passive"))
      (node (ref "C327") (pin "2") (pinfunction "2_2") (pintype "passive"))
      (node (ref "FR49") (pin "1") (pinfunction "1_1") (pintype "passive"))
      (node (ref "R138") (pin "2") (pinfunction "2_2") (pintype "passive"))
      (node (ref "XO1") (pin "5") (pinfunction "VDD_5") (pintype "passive"))
      (node (ref "XO2") (pin "4") (pinfunction "VDD_4") (pintype "passive"))
    )
    (net (code "62") (name "VCC1P8") (class "Default")
      (node (ref "C364") (pin "1") (pinfunction "1_1") (pintype "passive"))
      (node (ref "C365") (pin "1") (pinfunction "1_1") (pintype "passive"))
      (node (ref "C366") (pin "1") (pinfunction "1_1") (pintype "passive"))
      (node (ref "FR52") (pin "1") (pinfunction "1_1") (pintype "passive"))
      (node (ref "IC24") (pin "10") (pinfunction "VDDOB_10") (pintype "passive"))
      (node (ref "IC24") (pin "11") (pinfunction "VDDOA_11") (pintype "passive"))
      (node (ref "IC24") (pin "14") (pinfunction "VDDOD_14") (pintype "passive"))
    )
    (net (code "63") (name "VCC3P3_CLK") (class "Default")
      (node (ref "C345") (pin "2") (pinfunction "2_2") (pintype "passive"))
      (node (ref "C349") (pin "1") (pinfunction "1_1") (pintype "passive"))
      (node (ref "C350") (pin "1") (pinfunction "1_1") (pintype "passive"))
      (node (ref "C359") (pin "1") (pinfunction "1_1") (pintype "passive"))
      (node (ref "C360") (pin "1") (pinfunction "1_1") (pintype "passive"))
      (node (ref "FR49") (pin "2") (pinfunction "2_2") (pintype "passive"))
      (node (ref "FR51") (pin "1") (pinfunction "1_1") (pintype "passive"))
      (node (ref "FR54") (pin "1") (pinfunction "1_1") (pintype "passive"))
      (node (ref "FR55") (pin "1") (pinfunction "1_1") (pintype "passive"))
      (node (ref "IC23") (pin "16") (pinfunction "DVdd_16") (pintype "passive"))
      (node (ref "IC23") (pin "17") (pinfunction "DVdd_17") (pintype "passive"))
      (node (ref "IC24") (pin "18") (pinfunction "VDDOC_18") (pintype "passive"))
      (node (ref "IC24") (pin "20") (pinfunction "VDD_20") (pintype "passive"))
      (node (ref "R141") (pin "1") (pinfunction "1_1") (pintype "passive"))
      (node (ref "R153") (pin "2") (pinfunction "2_2") (pintype "passive"))
      (node (ref "R154") (pin "2") (pinfunction "2_2") (pintype "passive"))
    )
    (net (code "64") (name "VCC3P3_LMK") (class "Default")
      (node (ref "C334") (pin "2") (pinfunction "2_2") (pintype "passive"))
      (node (ref "C335") (pin "2") (pinfunction "2_2") (pintype "passive"))
      (node (ref "C336") (pin "2") (pinfunction "2_2") (pintype "passive"))
      (node (ref "C337") (pin "2") (pinfunction "2_2") (pintype "passive"))
      (node (ref "FR51") (pin "2") (pinfunction "2_2") (pintype "passive"))
      (node (ref "IC20") (pin "23") (pinfunction "Vdd_23") (pintype "passive"))
      (node (ref "IC20") (pin "8") (pinfunction "Vdd_8") (pintype "passive"))
      (node (ref "R136") (pin "2") (pinfunction "2_2") (pintype "passive"))
      (node (ref "R149") (pin "1") (pinfunction "1_1") (pintype "passive"))
    )
    (net (code "65") (name "VDIO_LMS_FPGA") (class "Default")
      (node (ref "FR50") (pin "1") (pinfunction "1_1") (pintype "passive"))
      (node (ref "R149") (pin "2") (pinfunction "2_2") (pintype "passive"))
    )
    (net (code "66") (name "VDIO_LMS_LMK") (class "Default")
      (node (ref "C329") (pin "2") (pinfunction "2_2") (pintype "passive"))
      (node (ref "C330") (pin "2") (pinfunction "2_2") (pintype "passive"))
      (node (ref "C331") (pin "2") (pinfunction "2_2") (pintype "passive"))
      (node (ref "C332") (pin "2") (pinfunction "2_2") (pintype "passive"))
      (node (ref "FR50") (pin "2") (pinfunction "2_2") (pintype "passive"))
      (node (ref "IC20") (pin "14") (pinfunction "Vddo_14") (pintype "passive"))
      (node (ref "IC20") (pin "18") (pinfunction "Vddo_18") (pintype "passive"))
    )
    (net (code "67") (name "unconnected-(IC20-OSCin-Pad9)") (class "Default")
      (node (ref "IC20") (pin "9") (pinfunction "OSCin_9") (pintype "passive+no_connect"))
    )
    (net (code "68") (name "unconnected-(IC20-OSCout-Pad10)") (class "Default")
      (node (ref "IC20") (pin "10") (pinfunction "OSCout_10") (pintype "passive+no_connect"))
    )
    (net (code "69") (name "unconnected-(IC24-INTR-Pad3)") (class "Default")
      (node (ref "IC24") (pin "3") (pinfunction "INTR_3") (pintype "passive+no_connect"))
    )
    (net (code "70") (name "unconnected-(XO1-T.S.-Pad3)") (class "Default")
      (node (ref "XO1") (pin "3") (pinfunction "T.S._3") (pintype "passive+no_connect"))
    )
  )
)
